# Pixie2313.net
KiCad netlist of a schematic drawn in EAGLE
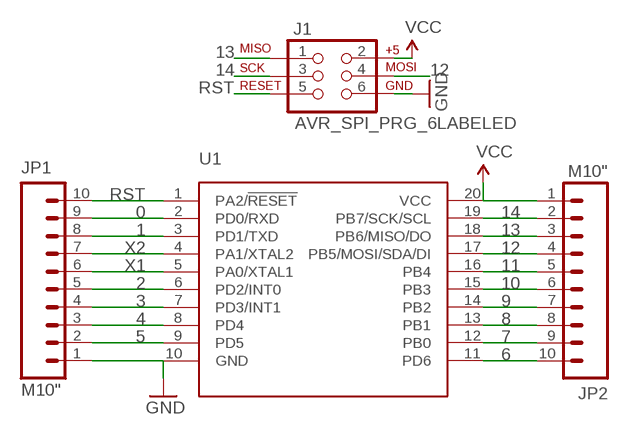
[diagram p0: schematic, sheet 1]

(export (version "E")
  (design (tool "Eeschema 10.0.6"))
  (components
    (comp (ref "J1")
      (value "AVR_SPI_PRG_6LABELED")
      (footprint "eagle-import:2X3-NS")
      (libsource (lib "eagle-import") (part "AVR_SPI_PRG_6LABELED"))
    )
    (comp (ref "JP1")
      (value "M10\"")
      (footprint "eagle-import:1X10")
      (libsource (lib "eagle-import") (part "M10{dblquote}"))
    )
    (comp (ref "JP2")
      (value "M10\"")
      (footprint "eagle-import:1X10")
      (libsource (lib "eagle-import") (part "M10{dblquote}"))
    )
    (comp (ref "U1")
      (value "ATTINY2313APTH")
      (footprint "eagle-import:DIL20")
      (libsource (lib "eagle-import") (part "ATTINY2313APTH"))
    )
  )
  (nets
    (net (code "1") (name "/0") (class "Default")
      (node (ref "JP1") (pin "9") (pinfunction "9_9") (pintype "passive"))
      (node (ref "U1") (pin "2") (pinfunction "PD0/RXD_2") (pintype "bidirectional"))
    )
    (net (code "2") (name "/1") (class "Default")
      (node (ref "JP1") (pin "8") (pinfunction "8_8") (pintype "passive"))
      (node (ref "U1") (pin "3") (pinfunction "PD1/TXD_3") (pintype "bidirectional"))
    )
    (net (code "3") (name "/2") (class "Default")
      (node (ref "JP1") (pin "5") (pinfunction "5_5") (pintype "passive"))
      (node (ref "U1") (pin "6") (pinfunction "PD2/INT0_6") (pintype "bidirectional"))
    )
    (net (code "4") (name "/3") (class "Default")
      (node (ref "JP1") (pin "4") (pinfunction "4_4") (pintype "passive"))
      (node (ref "U1") (pin "7") (pinfunction "PD3/INT1_7") (pintype "bidirectional"))
    )
    (net (code "5") (name "/4") (class "Default")
      (node (ref "JP1") (pin "3") (pinfunction "3_3") (pintype "passive"))
      (node (ref "U1") (pin "8") (pinfunction "PD4_8") (pintype "bidirectional"))
    )
    (net (code "6") (name "/5") (class "Default")
      (node (ref "JP1") (pin "2") (pinfunction "2_2") (pintype "passive"))
      (node (ref "U1") (pin "9") (pinfunction "PD5_9") (pintype "bidirectional"))
    )
    (net (code "7") (name "/6") (class "Default")
      (node (ref "JP2") (pin "10") (pinfunction "10_10") (pintype "passive"))
      (node (ref "U1") (pin "11") (pinfunction "PD6_11") (pintype "bidirectional"))
    )
    (net (code "8") (name "/7") (class "Default")
      (node (ref "JP2") (pin "9") (pinfunction "9_9") (pintype "passive"))
      (node (ref "U1") (pin "12") (pinfunction "PB0_12") (pintype "bidirectional"))
    )
    (net (code "9") (name "/8") (class "Default")
      (node (ref "JP2") (pin "8") (pinfunction "8_8") (pintype "passive"))
      (node (ref "U1") (pin "13") (pinfunction "PB1_13") (pintype "bidirectional"))
    )
    (net (code "10") (name "/9") (class "Default")
      (node (ref "JP2") (pin "7") (pinfunction "7_7") (pintype "passive"))
      (node (ref "U1") (pin "14") (pinfunction "PB2_14") (pintype "bidirectional"))
    )
    (net (code "11") (name "/10") (class "Default")
      (node (ref "JP2") (pin "6") (pinfunction "6_6") (pintype "passive"))
      (node (ref "U1") (pin "15") (pinfunction "PB3_15") (pintype "bidirectional"))
    )
    (net (code "12") (name "/11") (class "Default")
      (node (ref "JP2") (pin "5") (pinfunction "5_5") (pintype "passive"))
      (node (ref "U1") (pin "16") (pinfunction "PB4_16") (pintype "bidirectional"))
    )
    (net (code "13") (name "/12") (class "Default")
      (node (ref "J1") (pin "4") (pinfunction "4_4") (pintype "passive"))
      (node (ref "JP2") (pin "4") (pinfunction "4_4") (pintype "passive"))
      (node (ref "U1") (pin "17") (pinfunction "PB5/MOSI/SDA/DI_17") (pintype "bidirectional"))
    )
    (net (code "14") (name "/13") (class "Default")
      (node (ref "J1") (pin "1") (pinfunction "1_1") (pintype "passive"))
      (node (ref "JP2") (pin "3") (pinfunction "3_3") (pintype "passive"))
      (node (ref "U1") (pin "18") (pinfunction "PB6/MISO/DO_18") (pintype "bidirectional"))
    )
    (net (code "15") (name "/14") (class "Default")
      (node (ref "J1") (pin "3") (pinfunction "3_3") (pintype "passive"))
      (node (ref "JP2") (pin "2") (pinfunction "2_2") (pintype "passive"))
      (node (ref "U1") (pin "19") (pinfunction "PB7/SCK/SCL_19") (pintype "bidirectional"))
    )
    (net (code "16") (name "/RST") (class "Default")
      (node (ref "J1") (pin "5") (pinfunction "5_5") (pintype "passive"))
      (node (ref "JP1") (pin "10") (pinfunction "10_10") (pintype "passive"))
      (node (ref "U1") (pin "1") (pinfunction "PA2/~{RESET}_1") (pintype "bidirectional"))
    )
    (net (code "17") (name "/X1") (class "Default")
      (node (ref "JP1") (pin "6") (pinfunction "6_6") (pintype "passive"))
      (node (ref "U1") (pin "5") (pinfunction "PA0/XTAL1_5") (pintype "bidirectional"))
    )
    (net (code "18") (name "/X2") (class "Default")
      (node (ref "JP1") (pin "7") (pinfunction "7_7") (pintype "passive"))
      (node (ref "U1") (pin "4") (pinfunction "PA1/XTAL2_4") (pintype "bidirectional"))
    )
    (net (code "19") (name "GND") (class "Default")
      (node (ref "J1") (pin "6") (pinfunction "6_6") (pintype "passive"))
      (node (ref "JP1") (pin "1") (pinfunction "1_1") (pintype "passive"))
      (node (ref "U1") (pin "10") (pinfunction "GND_10") (pintype "bidirectional"))
    )
    (net (code "20") (name "VCC") (class "Default")
      (node (ref "J1") (pin "2") (pinfunction "2_2") (pintype "passive"))
      (node (ref "JP2") (pin "1") (pinfunction "1_1") (pintype "passive"))
      (node (ref "U1") (pin "20") (pinfunction "VCC_20") (pintype "bidirectional"))
    )
  )
)
